# smartstand-headphone-detection-rev-a.net
KiCad netlist of a schematic drawn in EAGLE
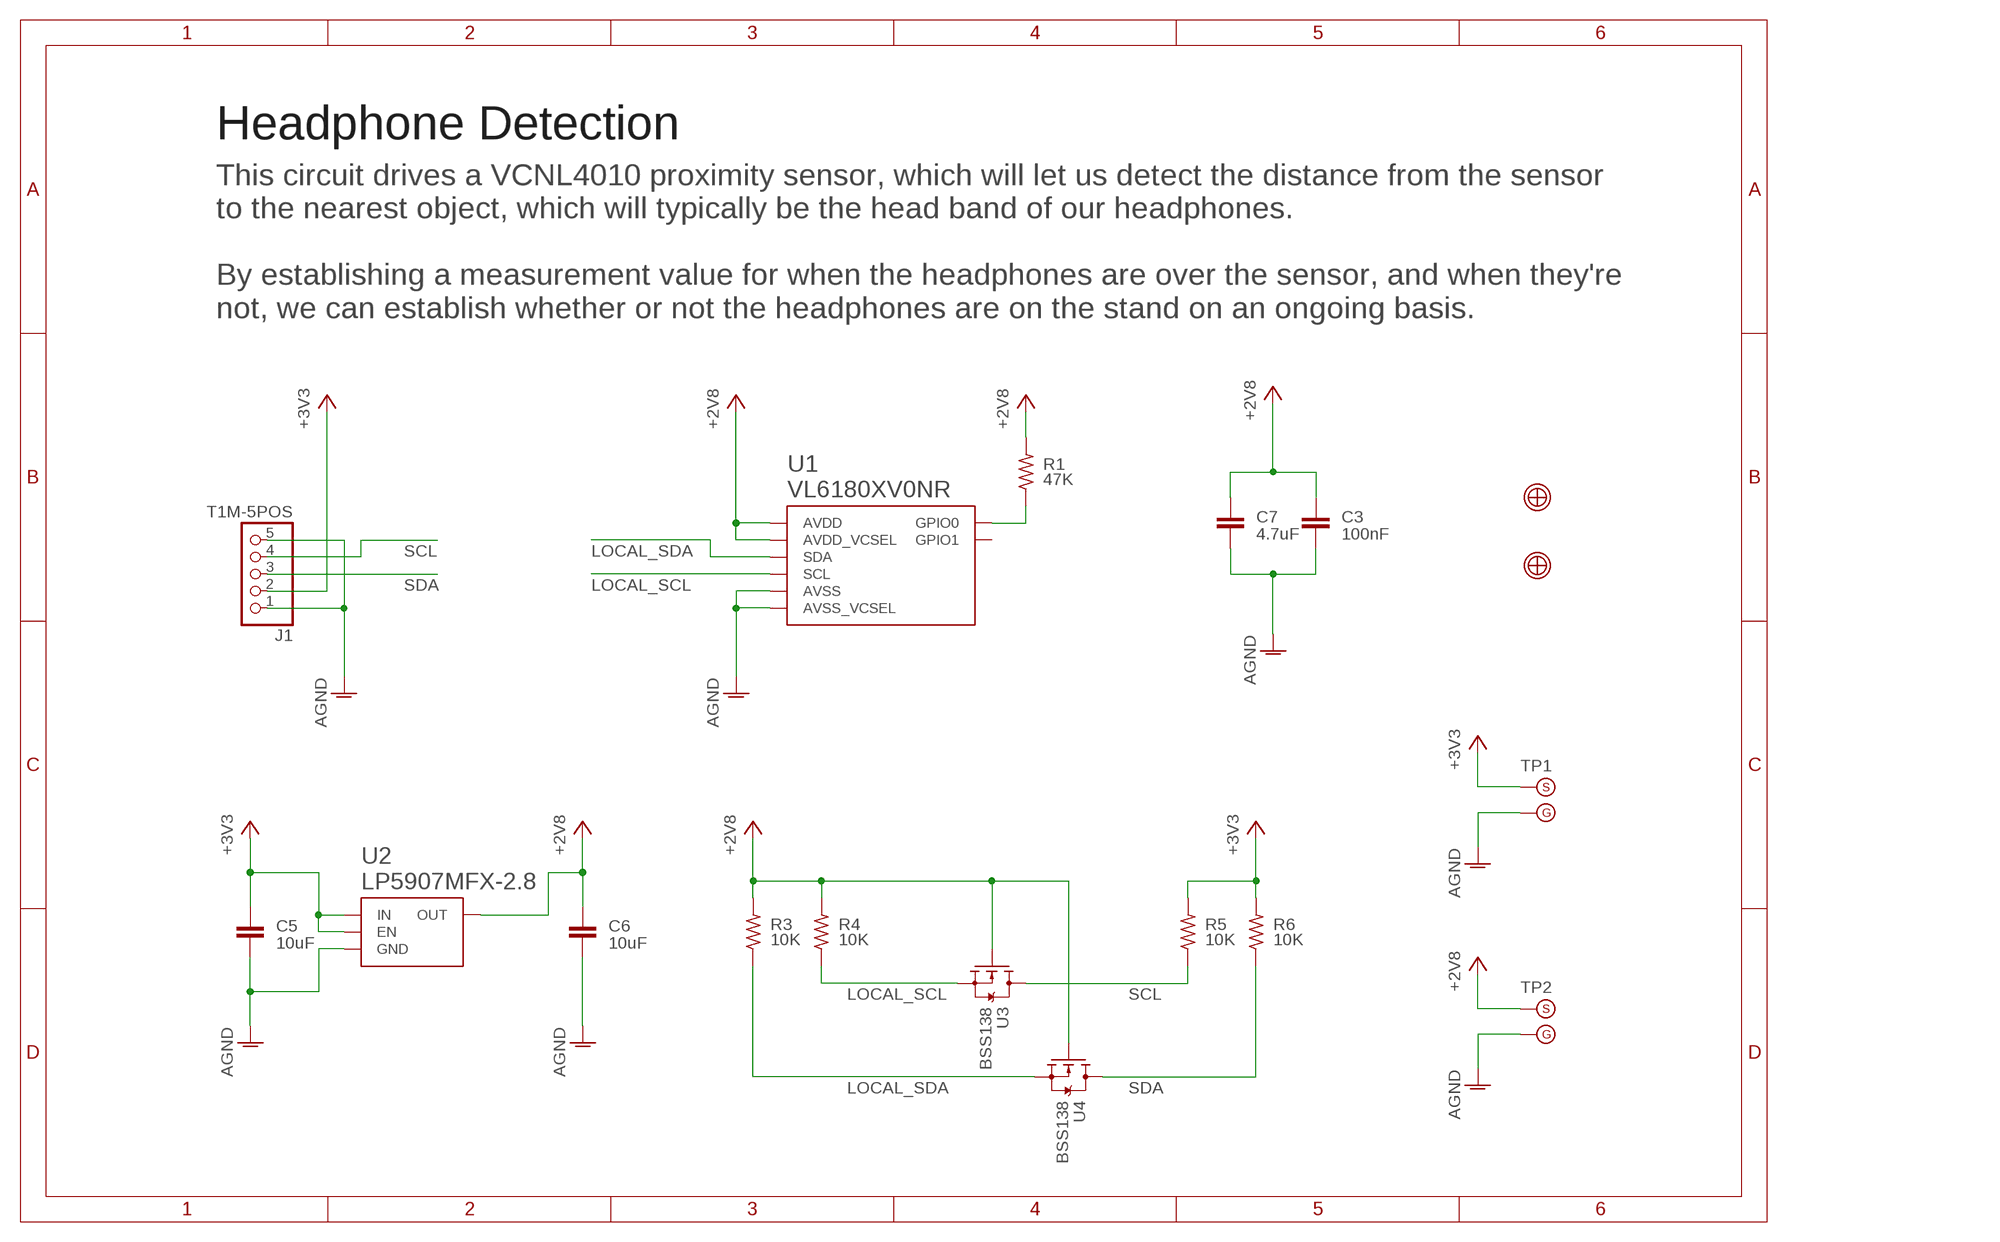
[diagram p0: schematic, sheet 1]

(export (version "E")
  (design (tool "Eeschema 10.0.6"))
  (components
    (comp (ref "C3")
      (value "100nF")
      (footprint "eagle-import:C0402")
      (libsource (lib "eagle-import") (part "CAPACITOR-0402"))
    )
    (comp (ref "C5")
      (value "10uF")
      (footprint "eagle-import:C0603")
      (libsource (lib "eagle-import") (part "CAPACITOR-0603"))
    )
    (comp (ref "C6")
      (value "10uF")
      (footprint "eagle-import:C0603")
      (libsource (lib "eagle-import") (part "CAPACITOR-0603"))
    )
    (comp (ref "C7")
      (value "4.7uF")
      (footprint "eagle-import:C0603")
      (libsource (lib "eagle-import") (part "CAPACITOR-0603"))
    )
    (comp (ref "J1")
      (value "T1M-5POS")
      (footprint "eagle-import:T1M-SINGLE-5POS")
      (libsource (lib "eagle-import") (part "T1M-5POS"))
    )
    (comp (ref "R1")
      (value "47K")
      (footprint "eagle-import:R0402")
      (libsource (lib "eagle-import") (part "RESISTOR-0402"))
    )
    (comp (ref "R3")
      (value "10K")
      (footprint "eagle-import:R0402")
      (libsource (lib "eagle-import") (part "RESISTOR-0402"))
    )
    (comp (ref "R4")
      (value "10K")
      (footprint "eagle-import:R0402")
      (libsource (lib "eagle-import") (part "RESISTOR-0402"))
    )
    (comp (ref "R5")
      (value "10K")
      (footprint "eagle-import:R0402")
      (libsource (lib "eagle-import") (part "RESISTOR-0402"))
    )
    (comp (ref "R6")
      (value "10K")
      (footprint "eagle-import:R0402")
      (libsource (lib "eagle-import") (part "RESISTOR-0402"))
    )
    (comp (ref "TP1")
      (value "TESTPOINT-WITH-GND")
      (footprint "eagle-import:TESTPOINT-1.5-WITH-GND")
      (libsource (lib "eagle-import") (part "TESTPOINT-WITH-GND"))
    )
    (comp (ref "TP2")
      (value "TESTPOINT-WITH-GND")
      (footprint "eagle-import:TESTPOINT-1.5-WITH-GND")
      (libsource (lib "eagle-import") (part "TESTPOINT-WITH-GND"))
    )
    (comp (ref "U$1")
      (value "FIDUCIAL-1MM")
      (footprint "eagle-import:FIDUCIAL_1MM")
      (libsource (lib "eagle-import") (part "FIDUCIAL-1MM"))
    )
    (comp (ref "U$2")
      (value "FIDUCIAL-1MM")
      (footprint "eagle-import:FIDUCIAL_1MM")
      (libsource (lib "eagle-import") (part "FIDUCIAL-1MM"))
    )
    (comp (ref "U1")
      (value "VL6180XV0NR")
      (footprint "eagle-import:VL6180X")
      (libsource (lib "eagle-import") (part "VL6180XV0NR"))
    )
    (comp (ref "U2")
      (value "LP5907MFX-2.8")
      (footprint "eagle-import:R-PDSO-G5-DBV")
      (libsource (lib "eagle-import") (part "LP5907MFX-2.8"))
    )
    (comp (ref "U3")
      (value "BSS138")
      (footprint "eagle-import:SOT23")
      (libsource (lib "eagle-import") (part "BSS138LT3G"))
    )
    (comp (ref "U4")
      (value "BSS138")
      (footprint "eagle-import:SOT23")
      (libsource (lib "eagle-import") (part "BSS138LT3G"))
    )
  )
  (nets
    (net (code "1") (name "+2V8") (class "Default")
      (node (ref "C3") (pin "1") (pinfunction "1_1") (pintype "passive"))
      (node (ref "C6") (pin "1") (pinfunction "1_1") (pintype "passive"))
      (node (ref "C7") (pin "1") (pinfunction "1_1") (pintype "passive"))
      (node (ref "R1") (pin "2") (pinfunction "2_2") (pintype "passive"))
      (node (ref "R3") (pin "2") (pinfunction "2_2") (pintype "passive"))
      (node (ref "R4") (pin "2") (pinfunction "2_2") (pintype "passive"))
      (node (ref "TP2") (pin "S") (pinfunction "S_S") (pintype "bidirectional"))
      (node (ref "U1") (pin "10") (pinfunction "AVDD_10") (pintype "bidirectional"))
      (node (ref "U1") (pin "8") (pinfunction "AVDD_VCSEL_8") (pintype "bidirectional"))
      (node (ref "U2") (pin "5") (pinfunction "OUT_5") (pintype "bidirectional"))
      (node (ref "U3") (pin "1") (pinfunction "G_1") (pintype "passive"))
      (node (ref "U4") (pin "1") (pinfunction "G_1") (pintype "passive"))
    )
    (net (code "2") (name "+3V3") (class "Default")
      (node (ref "C5") (pin "1") (pinfunction "1_1") (pintype "passive"))
      (node (ref "J1") (pin "2") (pinfunction "2_2") (pintype "passive"))
      (node (ref "R5") (pin "2") (pinfunction "2_2") (pintype "passive"))
      (node (ref "R6") (pin "2") (pinfunction "2_2") (pintype "passive"))
      (node (ref "TP1") (pin "S") (pinfunction "S_S") (pintype "bidirectional"))
      (node (ref "U2") (pin "1") (pinfunction "IN_1") (pintype "bidirectional"))
      (node (ref "U2") (pin "3") (pinfunction "EN_3") (pintype "bidirectional"))
    )
    (net (code "3") (name "/LOCAL_SCL") (class "Default")
      (node (ref "R4") (pin "1") (pinfunction "1_1") (pintype "passive"))
      (node (ref "U1") (pin "5") (pinfunction "SCL_5") (pintype "bidirectional"))
      (node (ref "U3") (pin "2") (pinfunction "S_2") (pintype "passive"))
    )
    (net (code "4") (name "/LOCAL_SDA") (class "Default")
      (node (ref "R3") (pin "1") (pinfunction "1_1") (pintype "passive"))
      (node (ref "U1") (pin "6") (pinfunction "SDA_6") (pintype "bidirectional"))
      (node (ref "U4") (pin "2") (pinfunction "S_2") (pintype "passive"))
    )
    (net (code "5") (name "/SCL") (class "Default")
      (node (ref "J1") (pin "4") (pinfunction "4_4") (pintype "passive"))
      (node (ref "R5") (pin "1") (pinfunction "1_1") (pintype "passive"))
      (node (ref "U3") (pin "3") (pinfunction "D_3") (pintype "passive"))
    )
    (net (code "6") (name "/SDA") (class "Default")
      (node (ref "J1") (pin "3") (pinfunction "3_3") (pintype "passive"))
      (node (ref "R6") (pin "1") (pinfunction "1_1") (pintype "passive"))
      (node (ref "U4") (pin "3") (pinfunction "D_3") (pintype "passive"))
    )
    (net (code "7") (name "AGND") (class "Default")
      (node (ref "C3") (pin "2") (pinfunction "2_2") (pintype "passive"))
      (node (ref "C5") (pin "2") (pinfunction "2_2") (pintype "passive"))
      (node (ref "C6") (pin "2") (pinfunction "2_2") (pintype "passive"))
      (node (ref "C7") (pin "2") (pinfunction "2_2") (pintype "passive"))
      (node (ref "J1") (pin "1") (pinfunction "1_1") (pintype "passive"))
      (node (ref "J1") (pin "5") (pinfunction "5_5") (pintype "passive"))
      (node (ref "TP1") (pin "G") (pinfunction "G_G") (pintype "bidirectional"))
      (node (ref "TP2") (pin "G") (pinfunction "G_G") (pintype "bidirectional"))
      (node (ref "U1") (pin "12") (pinfunction "AVSS_12") (pintype "bidirectional"))
      (node (ref "U1") (pin "9") (pinfunction "AVSS_VCSEL_9") (pintype "bidirectional"))
      (node (ref "U2") (pin "2") (pinfunction "GND_2") (pintype "bidirectional"))
    )
    (net (code "8") (name "Net-(U1-GPIO0)") (class "Default")
      (node (ref "R1") (pin "1") (pinfunction "1_1") (pintype "passive"))
      (node (ref "U1") (pin "4") (pinfunction "GPIO0_4") (pintype "bidirectional"))
    )
    (net (code "9") (name "unconnected-(U1-GPIO1-Pad1)") (class "Default")
      (node (ref "U1") (pin "1") (pinfunction "GPIO1_1") (pintype "bidirectional"))
    )
  )
)
